# eeZee_tiny.net
KiCad netlist of a schematic drawn in EAGLE
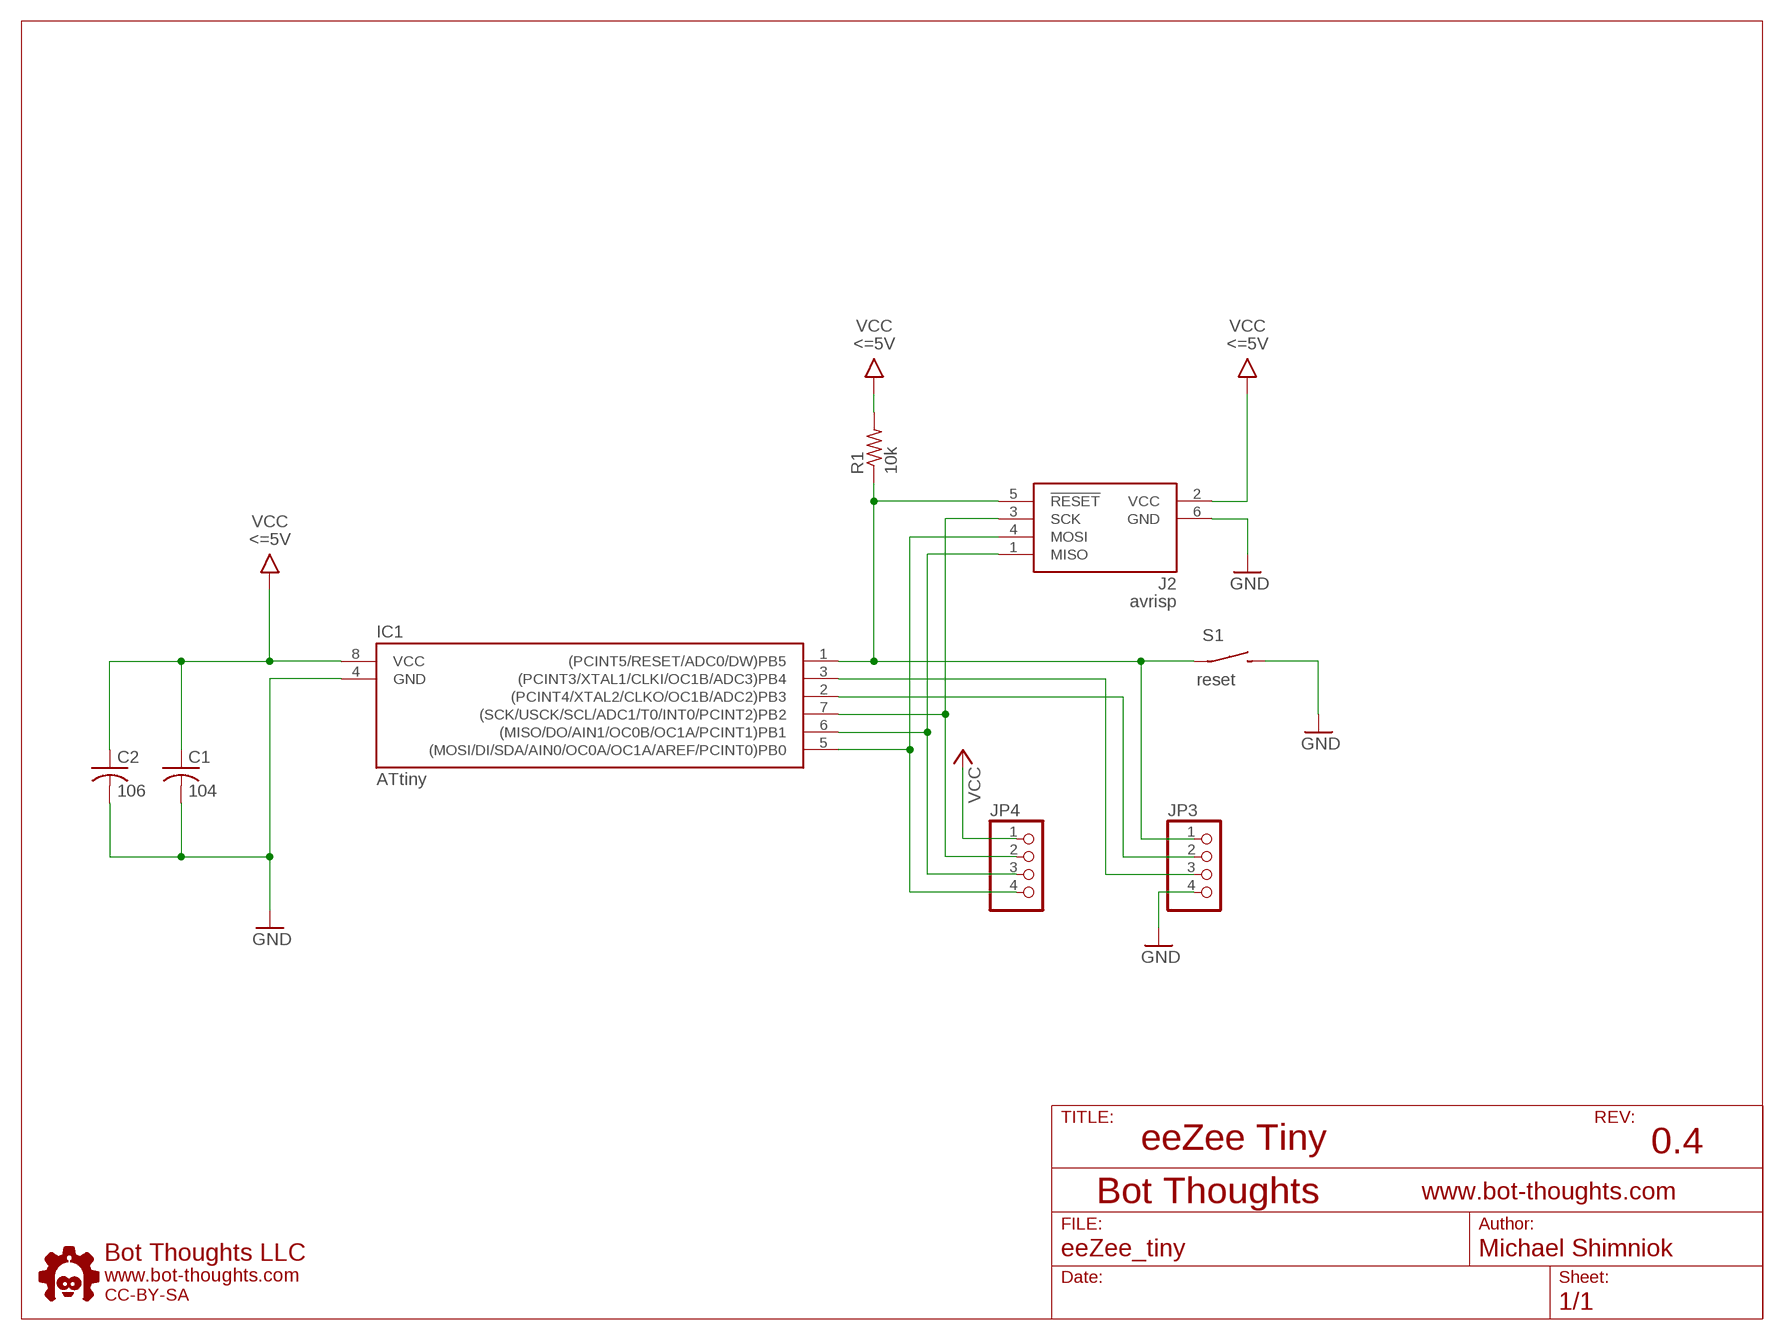
[diagram p0: schematic, sheet 1]

(export (version "E")
  (design (tool "Eeschema 10.0.6"))
  (components
    (comp (ref "C1")
      (value "104")
      (footprint "eagle-import:C0603")
      (fields (field (name "PARTNO") "0603YC104KAT2A"))
      (libsource (lib "eagle-import") (part "C-USC0603"))
    )
    (comp (ref "C2")
      (value "106")
      (footprint "eagle-import:C1206")
      (fields (field (name "PARTNO") "F930J107MBA"))
      (libsource (lib "eagle-import") (part "C-USC1206"))
    )
    (comp (ref "IC1")
      (value "ATtiny")
      (footprint "eagle-import:DIL08")
      (libsource (lib "eagle-import") (part "TINY25-20PU"))
    )
    (comp (ref "J2")
      (value "avrisp")
      (footprint "eagle-import:CON6P2R")
      (libsource (lib "eagle-import") (part "AVRISP6_COMPACT"))
    )
    (comp (ref "JP3")
      (value "PINHD-1X04_2.54-S")
      (footprint "eagle-import:1X04-S")
      (libsource (lib "eagle-import") (part "PINHD-1X04_2.54-S"))
    )
    (comp (ref "JP4")
      (value "PINHD-1X04_2.54-S")
      (footprint "eagle-import:1X04-S")
      (libsource (lib "eagle-import") (part "PINHD-1X04_2.54-S"))
    )
    (comp (ref "R1")
      (value "10k")
      (footprint "eagle-import:R0603")
      (fields (field (name "PARTNO") "ERJ-3GEYJ103V"))
      (libsource (lib "eagle-import") (part "R-US_R0603"))
    )
    (comp (ref "S1")
      (value "reset")
      (footprint "eagle-import:6MMTACTILE_RECT")
      (libsource (lib "eagle-import") (part "SPST_TAC_RECT1"))
    )
    (comp (ref "U$1")
      (value "BTLOGO-LOGO-MD")
      (footprint "eagle-import:BTLOGOM")
      (libsource (lib "eagle-import") (part "BTLOGO-LOGO-MD"))
    )
  )
  (nets
    (net (code "1") (name "<=5V") (class "Default")
      (node (ref "C1") (pin "1") (pinfunction "1_1") (pintype "passive"))
      (node (ref "C2") (pin "1") (pinfunction "1_1") (pintype "passive"))
      (node (ref "IC1") (pin "8") (pinfunction "VCC_8") (pintype "power_in"))
      (node (ref "J2") (pin "2") (pinfunction "VCC_2") (pintype "power_in"))
      (node (ref "JP4") (pin "1") (pinfunction "1_1") (pintype "passive"))
      (node (ref "R1") (pin "2") (pinfunction "2_2") (pintype "passive"))
    )
    (net (code "2") (name "GND") (class "Default")
      (node (ref "C1") (pin "2") (pinfunction "2_2") (pintype "passive"))
      (node (ref "C2") (pin "2") (pinfunction "2_2") (pintype "passive"))
      (node (ref "IC1") (pin "4") (pinfunction "GND_4") (pintype "power_in"))
      (node (ref "J2") (pin "6") (pinfunction "GND_6") (pintype "power_in"))
      (node (ref "JP3") (pin "4") (pinfunction "4_4") (pintype "passive"))
      (node (ref "S1") (pin "P$2") (pinfunction "S_P$2") (pintype "passive"))
    )
    (net (code "3") (name "Net-(IC1-(MISO{slash}DO{slash}AIN1{slash}OC0B{slash}OC1A{slash}PCINT1)PB1)") (class "Default")
      (node (ref "IC1") (pin "6") (pinfunction "(MISO/DO/AIN1/OC0B/OC1A/PCINT1)PB1_6") (pintype "bidirectional"))
      (node (ref "J2") (pin "1") (pinfunction "MISO_1") (pintype "input"))
      (node (ref "JP4") (pin "3") (pinfunction "3_3") (pintype "passive"))
    )
    (net (code "4") (name "Net-(IC1-(MOSI{slash}DI{slash}SDA{slash}AIN0{slash}OC0A{slash}OC1A{slash}AREF{slash}PCINT0)PB0)") (class "Default")
      (node (ref "IC1") (pin "5") (pinfunction "(MOSI/DI/SDA/AIN0/OC0A/OC1A/AREF/PCINT0)PB0_5") (pintype "bidirectional"))
      (node (ref "J2") (pin "4") (pinfunction "MOSI_4") (pintype "output"))
      (node (ref "JP4") (pin "4") (pinfunction "4_4") (pintype "passive"))
    )
    (net (code "5") (name "Net-(IC1-(PCINT3{slash}XTAL1{slash}CLKI{slash}OC1B{slash}ADC3)PB4)") (class "Default")
      (node (ref "IC1") (pin "3") (pinfunction "(PCINT3/XTAL1/CLKI/OC1B/ADC3)PB4_3") (pintype "bidirectional"))
      (node (ref "JP3") (pin "3") (pinfunction "3_3") (pintype "passive"))
    )
    (net (code "6") (name "Net-(IC1-(PCINT4{slash}XTAL2{slash}CLKO{slash}OC1B{slash}ADC2)PB3)") (class "Default")
      (node (ref "IC1") (pin "2") (pinfunction "(PCINT4/XTAL2/CLKO/OC1B/ADC2)PB3_2") (pintype "bidirectional"))
      (node (ref "JP3") (pin "2") (pinfunction "2_2") (pintype "passive"))
    )
    (net (code "7") (name "Net-(IC1-(PCINT5{slash}RESET{slash}ADC0{slash}DW)PB5)") (class "Default")
      (node (ref "IC1") (pin "1") (pinfunction "(PCINT5/RESET/ADC0/DW)PB5_1") (pintype "bidirectional"))
      (node (ref "J2") (pin "5") (pinfunction "~{RESET}_5") (pintype "output"))
      (node (ref "JP3") (pin "1") (pinfunction "1_1") (pintype "passive"))
      (node (ref "R1") (pin "1") (pinfunction "1_1") (pintype "passive"))
      (node (ref "S1") (pin "P$1") (pinfunction "P_P$1") (pintype "passive"))
    )
    (net (code "8") (name "Net-(IC1-(SCK{slash}USCK{slash}SCL{slash}ADC1{slash}T0{slash}INT0{slash}PCINT2)PB2)") (class "Default")
      (node (ref "IC1") (pin "7") (pinfunction "(SCK/USCK/SCL/ADC1/T0/INT0/PCINT2)PB2_7") (pintype "bidirectional"))
      (node (ref "J2") (pin "3") (pinfunction "SCK_3") (pintype "output"))
      (node (ref "JP4") (pin "2") (pinfunction "2_2") (pintype "passive"))
    )
  )
)
